# brake.net
KiCad netlist of a schematic drawn in Altium Designer
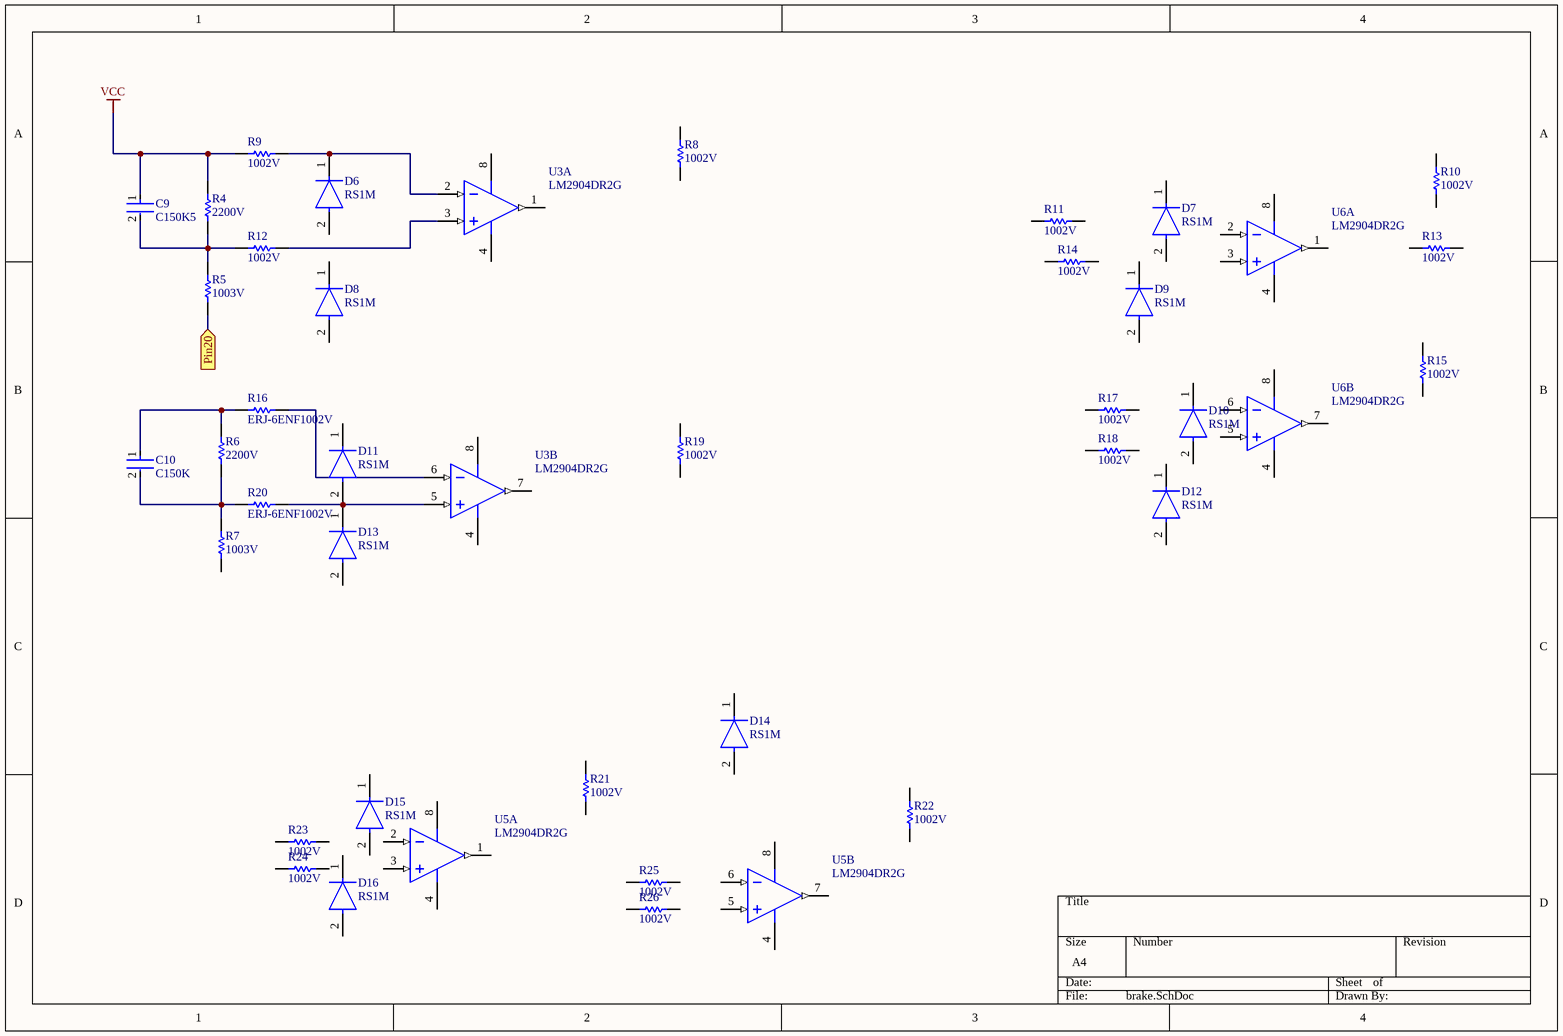
[diagram p0: brake.SchDoc]

(export (version "E")
  (design (tool "Eeschema 10.0.6"))
  (components
    (comp (ref "C9")
      (value "C150K5")
      (footprint "FP-C0805C-DN-MFG")
      (description "CAP CER 15PF 50V 10% NP0 0805")
      (fields
        (field (name "MANUFACTURER") "KEMET")
        (field (name "OCTOPART") "https://octopart.com/c0805c150k5gactu-kemet-6813460")
      )
      (libsource (lib "Altium Content Vault") (part "b4654b650e69147ec39a6b967a45e02"))
    )
    (comp (ref "C10")
      (value "C150K")
      (footprint "FP-C0805C-DN-MFG")
      (description "CAP CER 15PF 50V 10% NP0 0805")
      (fields
        (field (name "MANUFACTURER") "KEMET")
        (field (name "OCTOPART") "https://octopart.com/c0805c150k5gactu-kemet-6813460")
      )
      (libsource (lib "Altium Content Vault") (part "b4654b650e69147ec39a6b967a45e02"))
    )
    (comp (ref "D6")
      (value "RS1M")
      (footprint "FP-403AE-MFG")
      (description "Diode Standard 1000V 1A Surface Mount SMA (DO-214AC)")
      (fields (field (name "OCTOPART") "https://octopart.com/rs1m-on+semiconductor-84331238"))
      (libsource (lib "Altium Content Vault") (part "d7152d700b627762746794eb795d46e"))
    )
    (comp (ref "D7")
      (value "RS1M")
      (footprint "FP-403AE-MFG")
      (description "Diode Standard 1000V 1A Surface Mount SMA (DO-214AC)")
      (fields (field (name "OCTOPART") "https://octopart.com/rs1m-on+semiconductor-84331238"))
      (libsource (lib "Altium Content Vault") (part "d7152d700b627762746794eb795d46e"))
    )
    (comp (ref "D8")
      (value "RS1M")
      (footprint "FP-403AE-MFG")
      (description "Diode Standard 1000V 1A Surface Mount SMA (DO-214AC)")
      (fields (field (name "OCTOPART") "https://octopart.com/rs1m-on+semiconductor-84331238"))
      (libsource (lib "Altium Content Vault") (part "d7152d700b627762746794eb795d46e"))
    )
    (comp (ref "D9")
      (value "RS1M")
      (footprint "FP-403AE-MFG")
      (description "Diode Standard 1000V 1A Surface Mount SMA (DO-214AC)")
      (fields (field (name "OCTOPART") "https://octopart.com/rs1m-on+semiconductor-84331238"))
      (libsource (lib "Altium Content Vault") (part "d7152d700b627762746794eb795d46e"))
    )
    (comp (ref "D10")
      (value "RS1M")
      (footprint "FP-403AE-MFG")
      (description "Diode Standard 1000V 1A Surface Mount SMA (DO-214AC)")
      (fields (field (name "OCTOPART") "https://octopart.com/rs1m-on+semiconductor-84331238"))
      (libsource (lib "Altium Content Vault") (part "d7152d700b627762746794eb795d46e"))
    )
    (comp (ref "D11")
      (value "RS1M")
      (footprint "FP-403AE-MFG")
      (description "Diode Standard 1000V 1A Surface Mount SMA (DO-214AC)")
      (fields (field (name "OCTOPART") "https://octopart.com/rs1m-on+semiconductor-84331238"))
      (libsource (lib "Altium Content Vault") (part "d7152d700b627762746794eb795d46e"))
    )
    (comp (ref "D12")
      (value "RS1M")
      (footprint "FP-403AE-MFG")
      (description "Diode Standard 1000V 1A Surface Mount SMA (DO-214AC)")
      (fields (field (name "OCTOPART") "https://octopart.com/rs1m-on+semiconductor-84331238"))
      (libsource (lib "Altium Content Vault") (part "d7152d700b627762746794eb795d46e"))
    )
    (comp (ref "D13")
      (value "RS1M")
      (footprint "FP-403AE-MFG")
      (description "Diode Standard 1000V 1A Surface Mount SMA (DO-214AC)")
      (fields (field (name "OCTOPART") "https://octopart.com/rs1m-on+semiconductor-84331238"))
      (libsource (lib "Altium Content Vault") (part "d7152d700b627762746794eb795d46e"))
    )
    (comp (ref "D14")
      (value "RS1M")
      (footprint "FP-403AE-MFG")
      (description "Diode Standard 1000V 1A Surface Mount SMA (DO-214AC)")
      (fields (field (name "OCTOPART") "https://octopart.com/rs1m-on+semiconductor-84331238"))
      (libsource (lib "Altium Content Vault") (part "d7152d700b627762746794eb795d46e"))
    )
    (comp (ref "D15")
      (value "RS1M")
      (footprint "FP-403AE-MFG")
      (description "Diode Standard 1000V 1A Surface Mount SMA (DO-214AC)")
      (fields (field (name "OCTOPART") "https://octopart.com/rs1m-on+semiconductor-84331238"))
      (libsource (lib "Altium Content Vault") (part "d7152d700b627762746794eb795d46e"))
    )
    (comp (ref "D16")
      (value "RS1M")
      (footprint "FP-403AE-MFG")
      (description "Diode Standard 1000V 1A Surface Mount SMA (DO-214AC)")
      (fields (field (name "OCTOPART") "https://octopart.com/rs1m-on+semiconductor-84331238"))
      (libsource (lib "Altium Content Vault") (part "d7152d700b627762746794eb795d46e"))
    )
    (comp (ref "R4")
      (value "2200V")
      (footprint "RESC2013X70X40NL20T20")
      (fields (field (name "PART NUMBER") "ERJ6ENF2200V") (field (name "MANUFACTURER") "Panasonic"))
      (libsource (lib "Altium Content Vault") (part "RES"))
    )
    (comp (ref "R5")
      (value "1003V")
      (footprint "RESC2013X70X40LL20T20")
      (fields (field (name "PART NUMBER") "ERJ-6ENF1003V") (field (name "MANUFACTURER") "Panasonic"))
      (libsource (lib "Altium Content Vault") (part "RES"))
    )
    (comp (ref "R6")
      (value "2200V")
      (footprint "RESC2013X70X40NL20T20")
      (fields (field (name "PART NUMBER") "ERJ6ENF2200V") (field (name "MANUFACTURER") "Panasonic"))
      (libsource (lib "Altium Content Vault") (part "RES"))
    )
    (comp (ref "R7")
      (value "1003V")
      (footprint "RESC2013X70X40LL20T20")
      (fields (field (name "PART NUMBER") "ERJ-6ENF1003V") (field (name "MANUFACTURER") "Panasonic"))
      (libsource (lib "Altium Content Vault") (part "RES"))
    )
    (comp (ref "R8")
      (value "1002V")
      (footprint "RESC2013X70X40ML20T20")
      (fields (field (name "MANUFACTURER") "Panasonic") (field (name "PART NUMBER") "ERJ-6ENF1002V"))
      (libsource (lib "Altium Content Vault") (part "RES"))
    )
    (comp (ref "R9")
      (value "1002V")
      (footprint "RESC2013X70X40ML20T20")
      (fields (field (name "MANUFACTURER") "Panasonic") (field (name "PART NUMBER") "ERJ-6ENF1002V"))
      (libsource (lib "Altium Content Vault") (part "RES"))
    )
    (comp (ref "R10")
      (value "1002V")
      (footprint "RESC2013X70X40ML20T20")
      (fields (field (name "MANUFACTURER") "Panasonic") (field (name "PART NUMBER") "ERJ-6ENF1002V"))
      (libsource (lib "Altium Content Vault") (part "RES"))
    )
    (comp (ref "R11")
      (value "1002V")
      (footprint "RESC2013X70X40ML20T20")
      (fields (field (name "MANUFACTURER") "Panasonic") (field (name "PART NUMBER") "ERJ-6ENF1002V"))
      (libsource (lib "Altium Content Vault") (part "RES"))
    )
    (comp (ref "R12")
      (value "1002V")
      (footprint "RESC2013X70X40ML20T20")
      (fields (field (name "MANUFACTURER") "Panasonic") (field (name "PART NUMBER") "ERJ-6ENF1002V"))
      (libsource (lib "Altium Content Vault") (part "RES"))
    )
    (comp (ref "R13")
      (value "1002V")
      (footprint "RESC2013X70X40ML20T20")
      (fields (field (name "MANUFACTURER") "Panasonic") (field (name "PART NUMBER") "ERJ-6ENF1002V"))
      (libsource (lib "Altium Content Vault") (part "RES"))
    )
    (comp (ref "R14")
      (value "1002V")
      (footprint "RESC2013X70X40ML20T20")
      (fields (field (name "MANUFACTURER") "Panasonic") (field (name "PART NUMBER") "ERJ-6ENF1002V"))
      (libsource (lib "Altium Content Vault") (part "RES"))
    )
    (comp (ref "R15")
      (value "1002V")
      (footprint "RESC2013X70X40ML20T20")
      (fields (field (name "MANUFACTURER") "Panasonic") (field (name "PART NUMBER") "ERJ-6ENF1002V"))
      (libsource (lib "Altium Content Vault") (part "RES"))
    )
    (comp (ref "R16")
      (value "ERJ-6ENF1002V")
      (footprint "RESC2013X70X40ML20T20")
      (fields (field (name "MANUFACTURER") "Panasonic"))
      (libsource (lib "Altium Content Vault") (part "RES"))
    )
    (comp (ref "R17")
      (value "1002V")
      (footprint "RESC2013X70X40ML20T20")
      (fields (field (name "MANUFACTURER") "Panasonic") (field (name "PART NUMBER") "ERJ-6ENF1002V"))
      (libsource (lib "Altium Content Vault") (part "RES"))
    )
    (comp (ref "R18")
      (value "1002V")
      (footprint "RESC2013X70X40ML20T20")
      (fields (field (name "MANUFACTURER") "Panasonic") (field (name "PART NUMBER") "ERJ-6ENF1002V"))
      (libsource (lib "Altium Content Vault") (part "RES"))
    )
    (comp (ref "R19")
      (value "1002V")
      (footprint "RESC2013X70X40ML20T20")
      (fields (field (name "MANUFACTURER") "Panasonic") (field (name "PART NUMBER") "ERJ-6ENF1002V"))
      (libsource (lib "Altium Content Vault") (part "RES"))
    )
    (comp (ref "R20")
      (value "ERJ-6ENF1002V")
      (footprint "RESC2013X70X40ML20T20")
      (fields (field (name "MANUFACTURER") "Panasonic"))
      (libsource (lib "Altium Content Vault") (part "RES"))
    )
    (comp (ref "R21")
      (value "1002V")
      (footprint "RESC2013X70X40ML20T20")
      (fields (field (name "MANUFACTURER") "Panasonic") (field (name "PART NUMBER") "ERJ-6ENF1002V"))
      (libsource (lib "Altium Content Vault") (part "RES"))
    )
    (comp (ref "R22")
      (value "1002V")
      (footprint "RESC2013X70X40ML20T20")
      (fields (field (name "MANUFACTURER") "Panasonic") (field (name "PART NUMBER") "ERJ-6ENF1002V"))
      (libsource (lib "Altium Content Vault") (part "RES"))
    )
    (comp (ref "R23")
      (value "1002V")
      (footprint "RESC2013X70X40ML20T20")
      (fields (field (name "MANUFACTURER") "Panasonic") (field (name "PART NUMBER") "ERJ-6ENF1002V"))
      (libsource (lib "Altium Content Vault") (part "RES"))
    )
    (comp (ref "R24")
      (value "1002V")
      (footprint "RESC2013X70X40ML20T20")
      (fields (field (name "MANUFACTURER") "Panasonic") (field (name "PART NUMBER") "ERJ-6ENF1002V"))
      (libsource (lib "Altium Content Vault") (part "RES"))
    )
    (comp (ref "R25")
      (value "1002V")
      (footprint "RESC2013X70X40ML20T20")
      (fields (field (name "MANUFACTURER") "Panasonic") (field (name "PART NUMBER") "ERJ-6ENF1002V"))
      (libsource (lib "Altium Content Vault") (part "RES"))
    )
    (comp (ref "R26")
      (value "1002V")
      (footprint "RESC2013X70X40ML20T20")
      (fields (field (name "MANUFACTURER") "Panasonic") (field (name "PART NUMBER") "ERJ-6ENF1002V"))
      (libsource (lib "Altium Content Vault") (part "RES"))
    )
    (comp (ref "U3")
      (value "LM2904DR2G")
      (footprint "ONSC-SOIC-8-751-07_V")
      (fields (field (name "MANUFACTURER") "On Semiconductor"))
      (libsource (lib "Altium Content Vault") (part "ONSC-LM258_2904-8"))
    )
    (comp (ref "U5")
      (value "LM2904DR2G")
      (footprint "ONSC-SOIC-8-751-07_V")
      (fields (field (name "MANUFACTURER") "On Semiconductor"))
      (libsource (lib "Altium Content Vault") (part "ONSC-LM258_2904-8"))
    )
    (comp (ref "U6")
      (value "LM2904DR2G")
      (footprint "ONSC-SOIC-8-751-07_V")
      (fields (field (name "MANUFACTURER") "On Semiconductor"))
      (libsource (lib "Altium Content Vault") (part "ONSC-LM258_2904-8"))
    )
  )
  (nets
    (net (code "1") (name "/Pin20") (class "Default")
      (node (ref "R5") (pin "1") (pinfunction "1_1") (pintype "passive"))
    )
    (net (code "2") (name "Net-(C9-Pad2)") (class "Default")
      (node (ref "C9") (pin "2") (pinfunction "2_2") (pintype "passive"))
      (node (ref "R12") (pin "1") (pinfunction "1_1") (pintype "passive"))
      (node (ref "R4") (pin "1") (pinfunction "1_1") (pintype "passive"))
      (node (ref "R5") (pin "2") (pinfunction "2_2") (pintype "passive"))
    )
    (net (code "3") (name "Net-(C10-Pad1)") (class "Default")
      (node (ref "C10") (pin "1") (pinfunction "1_1") (pintype "passive"))
      (node (ref "R16") (pin "1") (pinfunction "1_1") (pintype "passive"))
      (node (ref "R6") (pin "2") (pinfunction "2_2") (pintype "passive"))
    )
    (net (code "4") (name "Net-(C10-Pad2)") (class "Default")
      (node (ref "C10") (pin "2") (pinfunction "2_2") (pintype "passive"))
      (node (ref "R20") (pin "1") (pinfunction "1_1") (pintype "passive"))
      (node (ref "R6") (pin "1") (pinfunction "1_1") (pintype "passive"))
      (node (ref "R7") (pin "2") (pinfunction "2_2") (pintype "passive"))
    )
    (net (code "5") (name "Net-(D6-C)") (class "Default")
      (node (ref "D6") (pin "1") (pinfunction "C_1") (pintype "passive"))
      (node (ref "R9") (pin "2") (pinfunction "2_2") (pintype "passive"))
      (node (ref "U3") (pin "2") (pinfunction "INA-_2") (pintype "input"))
    )
    (net (code "6") (name "Net-(D11-A)") (class "Default")
      (node (ref "D11") (pin "2") (pinfunction "A_2") (pintype "passive"))
      (node (ref "D13") (pin "1") (pinfunction "C_1") (pintype "passive"))
      (node (ref "R20") (pin "2") (pinfunction "2_2") (pintype "passive"))
      (node (ref "U3") (pin "5") (pinfunction "INB+_5") (pintype "input"))
    )
    (net (code "7") (name "Net-(U3A-INA+)") (class "Default")
      (node (ref "R12") (pin "2") (pinfunction "2_2") (pintype "passive"))
      (node (ref "U3") (pin "3") (pinfunction "INA+_3") (pintype "input"))
    )
    (net (code "8") (name "Net-(U3B-INB-)") (class "Default")
      (node (ref "R16") (pin "2") (pinfunction "2_2") (pintype "passive"))
      (node (ref "U3") (pin "6") (pinfunction "INB-_6") (pintype "input"))
    )
    (net (code "9") (name "VCC") (class "Default")
      (node (ref "C9") (pin "1") (pinfunction "1_1") (pintype "passive"))
      (node (ref "R4") (pin "2") (pinfunction "2_2") (pintype "passive"))
      (node (ref "R9") (pin "1") (pinfunction "1_1") (pintype "passive"))
    )
    (net (code "10") (name "unconnected-(D6-A-Pad2)") (class "Default")
      (node (ref "D6") (pin "2") (pinfunction "A_2") (pintype "passive"))
    )
    (net (code "11") (name "unconnected-(D7-A-Pad2)") (class "Default")
      (node (ref "D7") (pin "2") (pinfunction "A_2") (pintype "passive"))
    )
    (net (code "12") (name "unconnected-(D7-C-Pad1)") (class "Default")
      (node (ref "D7") (pin "1") (pinfunction "C_1") (pintype "passive"))
    )
    (net (code "13") (name "unconnected-(D8-A-Pad2)") (class "Default")
      (node (ref "D8") (pin "2") (pinfunction "A_2") (pintype "passive"))
    )
    (net (code "14") (name "unconnected-(D8-C-Pad1)") (class "Default")
      (node (ref "D8") (pin "1") (pinfunction "C_1") (pintype "passive"))
    )
    (net (code "15") (name "unconnected-(D9-A-Pad2)") (class "Default")
      (node (ref "D9") (pin "2") (pinfunction "A_2") (pintype "passive"))
    )
    (net (code "16") (name "unconnected-(D9-C-Pad1)") (class "Default")
      (node (ref "D9") (pin "1") (pinfunction "C_1") (pintype "passive"))
    )
    (net (code "17") (name "unconnected-(D10-A-Pad2)") (class "Default")
      (node (ref "D10") (pin "2") (pinfunction "A_2") (pintype "passive"))
    )
    (net (code "18") (name "unconnected-(D10-C-Pad1)") (class "Default")
      (node (ref "D10") (pin "1") (pinfunction "C_1") (pintype "passive"))
    )
    (net (code "19") (name "unconnected-(D11-C-Pad1)") (class "Default")
      (node (ref "D11") (pin "1") (pinfunction "C_1") (pintype "passive"))
    )
    (net (code "20") (name "unconnected-(D12-A-Pad2)") (class "Default")
      (node (ref "D12") (pin "2") (pinfunction "A_2") (pintype "passive"))
    )
    (net (code "21") (name "unconnected-(D12-C-Pad1)") (class "Default")
      (node (ref "D12") (pin "1") (pinfunction "C_1") (pintype "passive"))
    )
    (net (code "22") (name "unconnected-(D13-A-Pad2)") (class "Default")
      (node (ref "D13") (pin "2") (pinfunction "A_2") (pintype "passive"))
    )
    (net (code "23") (name "unconnected-(D14-A-Pad2)") (class "Default")
      (node (ref "D14") (pin "2") (pinfunction "A_2") (pintype "passive"))
    )
    (net (code "24") (name "unconnected-(D14-C-Pad1)") (class "Default")
      (node (ref "D14") (pin "1") (pinfunction "C_1") (pintype "passive"))
    )
    (net (code "25") (name "unconnected-(D15-A-Pad2)") (class "Default")
      (node (ref "D15") (pin "2") (pinfunction "A_2") (pintype "passive"))
    )
    (net (code "26") (name "unconnected-(D15-C-Pad1)") (class "Default")
      (node (ref "D15") (pin "1") (pinfunction "C_1") (pintype "passive"))
    )
    (net (code "27") (name "unconnected-(D16-A-Pad2)") (class "Default")
      (node (ref "D16") (pin "2") (pinfunction "A_2") (pintype "passive"))
    )
    (net (code "28") (name "unconnected-(D16-C-Pad1)") (class "Default")
      (node (ref "D16") (pin "1") (pinfunction "C_1") (pintype "passive"))
    )
    (net (code "29") (name "unconnected-(R7-Pad1)") (class "Default")
      (node (ref "R7") (pin "1") (pinfunction "1_1") (pintype "passive"))
    )
    (net (code "30") (name "unconnected-(R8-Pad1)") (class "Default")
      (node (ref "R8") (pin "1") (pinfunction "1_1") (pintype "passive"))
    )
    (net (code "31") (name "unconnected-(R8-Pad2)") (class "Default")
      (node (ref "R8") (pin "2") (pinfunction "2_2") (pintype "passive"))
    )
    (net (code "32") (name "unconnected-(R10-Pad1)") (class "Default")
      (node (ref "R10") (pin "1") (pinfunction "1_1") (pintype "passive"))
    )
    (net (code "33") (name "unconnected-(R10-Pad2)") (class "Default")
      (node (ref "R10") (pin "2") (pinfunction "2_2") (pintype "passive"))
    )
    (net (code "34") (name "unconnected-(R11-Pad1)") (class "Default")
      (node (ref "R11") (pin "1") (pinfunction "1_1") (pintype "passive"))
    )
    (net (code "35") (name "unconnected-(R11-Pad2)") (class "Default")
      (node (ref "R11") (pin "2") (pinfunction "2_2") (pintype "passive"))
    )
    (net (code "36") (name "unconnected-(R13-Pad1)") (class "Default")
      (node (ref "R13") (pin "1") (pinfunction "1_1") (pintype "passive"))
    )
    (net (code "37") (name "unconnected-(R13-Pad2)") (class "Default")
      (node (ref "R13") (pin "2") (pinfunction "2_2") (pintype "passive"))
    )
    (net (code "38") (name "unconnected-(R14-Pad1)") (class "Default")
      (node (ref "R14") (pin "1") (pinfunction "1_1") (pintype "passive"))
    )
    (net (code "39") (name "unconnected-(R14-Pad2)") (class "Default")
      (node (ref "R14") (pin "2") (pinfunction "2_2") (pintype "passive"))
    )
    (net (code "40") (name "unconnected-(R15-Pad1)") (class "Default")
      (node (ref "R15") (pin "1") (pinfunction "1_1") (pintype "passive"))
    )
    (net (code "41") (name "unconnected-(R15-Pad2)") (class "Default")
      (node (ref "R15") (pin "2") (pinfunction "2_2") (pintype "passive"))
    )
    (net (code "42") (name "unconnected-(R17-Pad1)") (class "Default")
      (node (ref "R17") (pin "1") (pinfunction "1_1") (pintype "passive"))
    )
    (net (code "43") (name "unconnected-(R17-Pad2)") (class "Default")
      (node (ref "R17") (pin "2") (pinfunction "2_2") (pintype "passive"))
    )
    (net (code "44") (name "unconnected-(R18-Pad1)") (class "Default")
      (node (ref "R18") (pin "1") (pinfunction "1_1") (pintype "passive"))
    )
    (net (code "45") (name "unconnected-(R18-Pad2)") (class "Default")
      (node (ref "R18") (pin "2") (pinfunction "2_2") (pintype "passive"))
    )
    (net (code "46") (name "unconnected-(R19-Pad1)") (class "Default")
      (node (ref "R19") (pin "1") (pinfunction "1_1") (pintype "passive"))
    )
    (net (code "47") (name "unconnected-(R19-Pad2)") (class "Default")
      (node (ref "R19") (pin "2") (pinfunction "2_2") (pintype "passive"))
    )
    (net (code "48") (name "unconnected-(R21-Pad1)") (class "Default")
      (node (ref "R21") (pin "1") (pinfunction "1_1") (pintype "passive"))
    )
    (net (code "49") (name "unconnected-(R21-Pad2)") (class "Default")
      (node (ref "R21") (pin "2") (pinfunction "2_2") (pintype "passive"))
    )
    (net (code "50") (name "unconnected-(R22-Pad1)") (class "Default")
      (node (ref "R22") (pin "1") (pinfunction "1_1") (pintype "passive"))
    )
    (net (code "51") (name "unconnected-(R22-Pad2)") (class "Default")
      (node (ref "R22") (pin "2") (pinfunction "2_2") (pintype "passive"))
    )
    (net (code "52") (name "unconnected-(R23-Pad1)") (class "Default")
      (node (ref "R23") (pin "1") (pinfunction "1_1") (pintype "passive"))
    )
    (net (code "53") (name "unconnected-(R23-Pad2)") (class "Default")
      (node (ref "R23") (pin "2") (pinfunction "2_2") (pintype "passive"))
    )
    (net (code "54") (name "unconnected-(R24-Pad1)") (class "Default")
      (node (ref "R24") (pin "1") (pinfunction "1_1") (pintype "passive"))
    )
    (net (code "55") (name "unconnected-(R24-Pad2)") (class "Default")
      (node (ref "R24") (pin "2") (pinfunction "2_2") (pintype "passive"))
    )
    (net (code "56") (name "unconnected-(R25-Pad1)") (class "Default")
      (node (ref "R25") (pin "1") (pinfunction "1_1") (pintype "passive"))
    )
    (net (code "57") (name "unconnected-(R25-Pad2)") (class "Default")
      (node (ref "R25") (pin "2") (pinfunction "2_2") (pintype "passive"))
    )
    (net (code "58") (name "unconnected-(R26-Pad1)") (class "Default")
      (node (ref "R26") (pin "1") (pinfunction "1_1") (pintype "passive"))
    )
    (net (code "59") (name "unconnected-(R26-Pad2)") (class "Default")
      (node (ref "R26") (pin "2") (pinfunction "2_2") (pintype "passive"))
    )
    (net (code "60") (name "unconnected-(U3A-OUTA-Pad1)") (class "Default")
      (node (ref "U3") (pin "1") (pinfunction "OUTA_1") (pintype "output"))
    )
    (net (code "61") (name "unconnected-(U3A-VCC-Pad8)") (class "Default")
      (node (ref "U3") (pin "8") (pinfunction "VCC_8") (pintype "power_in"))
    )
    (net (code "62") (name "unconnected-(U3A-VEE{slash}GND-Pad4)") (class "Default")
      (node (ref "U3") (pin "4") (pinfunction "VEE/GND_4") (pintype "power_in"))
    )
    (net (code "63") (name "unconnected-(U3B-OUTB-Pad7)") (class "Default")
      (node (ref "U3") (pin "7") (pinfunction "OUTB_7") (pintype "output"))
    )
    (net (code "64") (name "unconnected-(U3B-VCC-Pad8)") (class "Default")
      (node (ref "U3") (pin "8") (pinfunction "VCC_8") (pintype "power_in"))
    )
    (net (code "65") (name "unconnected-(U3B-VEE{slash}GND-Pad4)") (class "Default")
      (node (ref "U3") (pin "4") (pinfunction "VEE/GND_4") (pintype "power_in"))
    )
    (net (code "66") (name "unconnected-(U5A-INA+-Pad3)") (class "Default")
      (node (ref "U5") (pin "3") (pinfunction "INA+_3") (pintype "input"))
    )
    (net (code "67") (name "unconnected-(U5A-INA--Pad2)") (class "Default")
      (node (ref "U5") (pin "2") (pinfunction "INA-_2") (pintype "input"))
    )
    (net (code "68") (name "unconnected-(U5A-OUTA-Pad1)") (class "Default")
      (node (ref "U5") (pin "1") (pinfunction "OUTA_1") (pintype "output"))
    )
    (net (code "69") (name "unconnected-(U5A-VCC-Pad8)") (class "Default")
      (node (ref "U5") (pin "8") (pinfunction "VCC_8") (pintype "power_in"))
    )
    (net (code "70") (name "unconnected-(U5A-VEE{slash}GND-Pad4)") (class "Default")
      (node (ref "U5") (pin "4") (pinfunction "VEE/GND_4") (pintype "power_in"))
    )
    (net (code "71") (name "unconnected-(U5B-INB+-Pad5)") (class "Default")
      (node (ref "U5") (pin "5") (pinfunction "INB+_5") (pintype "input"))
    )
    (net (code "72") (name "unconnected-(U5B-INB--Pad6)") (class "Default")
      (node (ref "U5") (pin "6") (pinfunction "INB-_6") (pintype "input"))
    )
    (net (code "73") (name "unconnected-(U5B-OUTB-Pad7)") (class "Default")
      (node (ref "U5") (pin "7") (pinfunction "OUTB_7") (pintype "output"))
    )
    (net (code "74") (name "unconnected-(U5B-VCC-Pad8)") (class "Default")
      (node (ref "U5") (pin "8") (pinfunction "VCC_8") (pintype "power_in"))
    )
    (net (code "75") (name "unconnected-(U5B-VEE{slash}GND-Pad4)") (class "Default")
      (node (ref "U5") (pin "4") (pinfunction "VEE/GND_4") (pintype "power_in"))
    )
    (net (code "76") (name "unconnected-(U6A-INA+-Pad3)") (class "Default")
      (node (ref "U6") (pin "3") (pinfunction "INA+_3") (pintype "input"))
    )
    (net (code "77") (name "unconnected-(U6A-INA--Pad2)") (class "Default")
      (node (ref "U6") (pin "2") (pinfunction "INA-_2") (pintype "input"))
    )
    (net (code "78") (name "unconnected-(U6A-OUTA-Pad1)") (class "Default")
      (node (ref "U6") (pin "1") (pinfunction "OUTA_1") (pintype "output"))
    )
    (net (code "79") (name "unconnected-(U6A-VCC-Pad8)") (class "Default")
      (node (ref "U6") (pin "8") (pinfunction "VCC_8") (pintype "power_in"))
    )
    (net (code "80") (name "unconnected-(U6A-VEE{slash}GND-Pad4)") (class "Default")
      (node (ref "U6") (pin "4") (pinfunction "VEE/GND_4") (pintype "power_in"))
    )
    (net (code "81") (name "unconnected-(U6B-INB+-Pad5)") (class "Default")
      (node (ref "U6") (pin "5") (pinfunction "INB+_5") (pintype "input"))
    )
    (net (code "82") (name "unconnected-(U6B-INB--Pad6)") (class "Default")
      (node (ref "U6") (pin "6") (pinfunction "INB-_6") (pintype "input"))
    )
    (net (code "83") (name "unconnected-(U6B-OUTB-Pad7)") (class "Default")
      (node (ref "U6") (pin "7") (pinfunction "OUTB_7") (pintype "output"))
    )
    (net (code "84") (name "unconnected-(U6B-VCC-Pad8)") (class "Default")
      (node (ref "U6") (pin "8") (pinfunction "VCC_8") (pintype "power_in"))
    )
    (net (code "85") (name "unconnected-(U6B-VEE{slash}GND-Pad4)") (class "Default")
      (node (ref "U6") (pin "4") (pinfunction "VEE/GND_4") (pintype "power_in"))
    )
  )
)
